# EurorackWizard.net
KiCad netlist of a schematic drawn in EAGLE
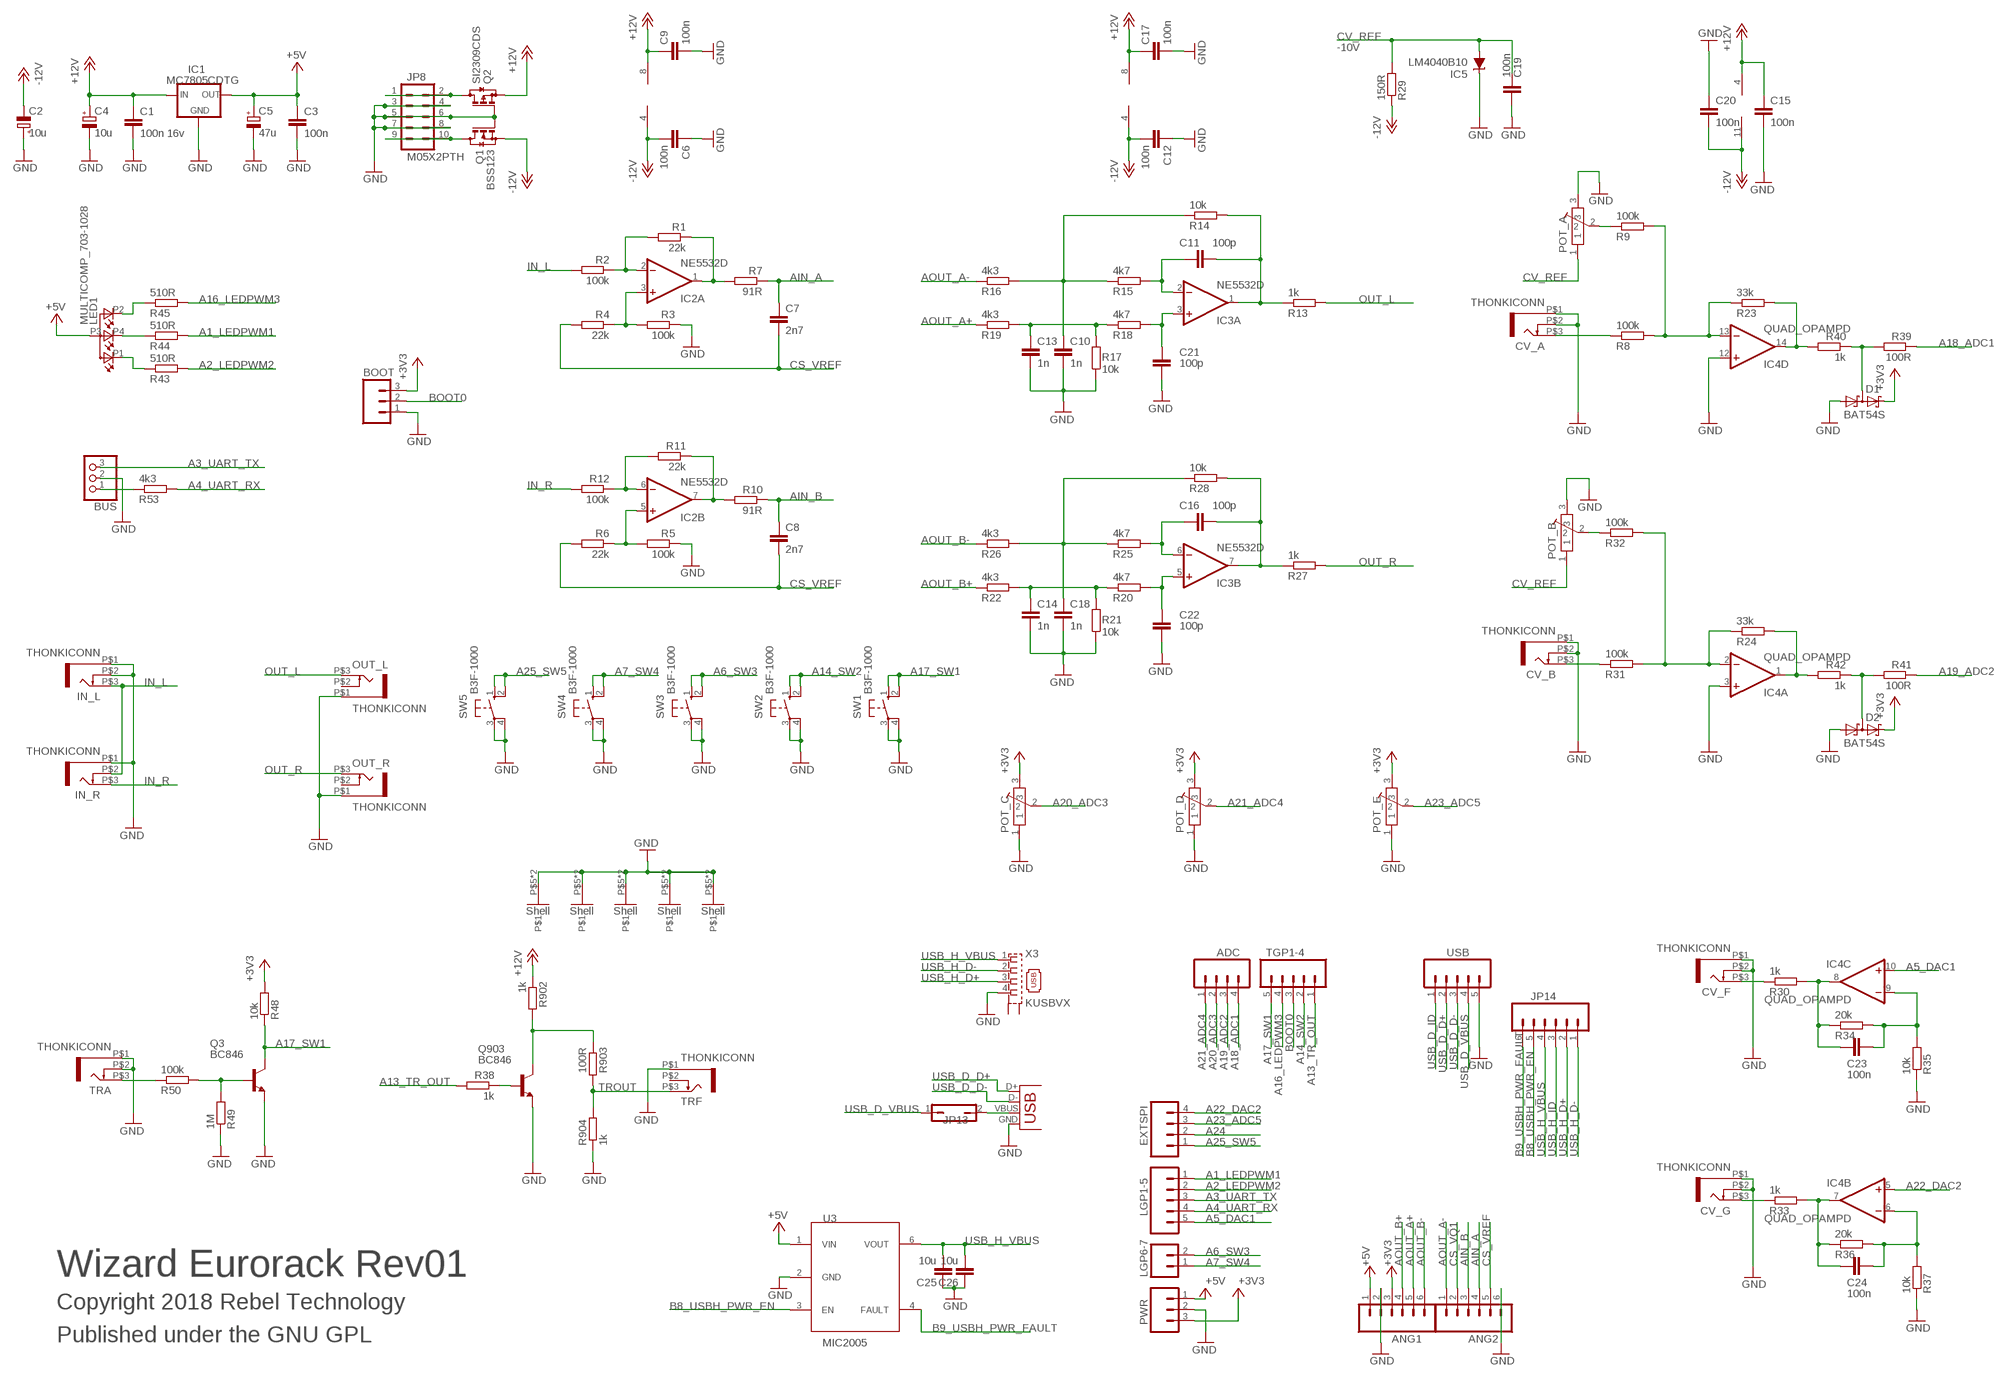
[diagram p0: schematic, sheet 1]

(export (version "E")
  (design (tool "Eeschema 10.0.6"))
  (components
    (comp (ref "ADC")
      (value "M04PTH")
      (footprint "eagle-import:1X04")
      (libsource (lib "eagle-import") (part "M04PTH"))
    )
    (comp (ref "ANG1")
      (value "M06SIP")
      (footprint "eagle-import:1X06")
      (libsource (lib "eagle-import") (part "M06SIP"))
    )
    (comp (ref "ANG2")
      (value "M06SIP")
      (footprint "eagle-import:1X06")
      (libsource (lib "eagle-import") (part "M06SIP"))
    )
    (comp (ref "BOOT")
      (value "M03PTH")
      (footprint "eagle-import:1X03")
      (libsource (lib "eagle-import") (part "M03PTH"))
    )
    (comp (ref "BUS")
      (value "CON-JST-1X03PH-TH")
      (footprint "eagle-import:JST-B3B-PH-KL")
      (libsource (lib "eagle-import") (part "CON-JST-1X03PH-TH"))
    )
    (comp (ref "C1")
      (value "100n 16v")
      (footprint "eagle-import:C0603")
      (libsource (lib "eagle-import") (part "C-EUC0603"))
    )
    (comp (ref "C2")
      (value "10u")
      (footprint "eagle-import:CPOL-5")
      (libsource (lib "eagle-import") (part "CPOL-EU153CLV-0505"))
    )
    (comp (ref "C3")
      (value "100n")
      (footprint "eagle-import:C0603")
      (libsource (lib "eagle-import") (part "C-EUC0603"))
    )
    (comp (ref "C4")
      (value "10u")
      (footprint "eagle-import:CPOL-5")
      (libsource (lib "eagle-import") (part "CPOL-EU153CLV-0505"))
    )
    (comp (ref "C5")
      (value "47u")
      (footprint "eagle-import:PANASONIC_B")
      (libsource (lib "eagle-import") (part "rcl_CPOL-EUB"))
    )
    (comp (ref "C6")
      (value "100n")
      (footprint "eagle-import:C0603")
      (libsource (lib "eagle-import") (part "resistor_C-EUC0603"))
    )
    (comp (ref "C7")
      (value "2n7")
      (footprint "eagle-import:C0603")
      (libsource (lib "eagle-import") (part "resistor_C-EUC0603"))
    )
    (comp (ref "C8")
      (value "2n7")
      (footprint "eagle-import:C0603")
      (libsource (lib "eagle-import") (part "resistor_C-EUC0603"))
    )
    (comp (ref "C9")
      (value "100n")
      (footprint "eagle-import:C0603")
      (libsource (lib "eagle-import") (part "resistor_C-EUC0603"))
    )
    (comp (ref "C10")
      (value "1n")
      (footprint "eagle-import:C0603")
      (libsource (lib "eagle-import") (part "resistor_C-EUC0603"))
    )
    (comp (ref "C11")
      (value "100p")
      (footprint "eagle-import:C0603")
      (libsource (lib "eagle-import") (part "resistor_C-EUC0603"))
    )
    (comp (ref "C12")
      (value "100n")
      (footprint "eagle-import:C0603")
      (libsource (lib "eagle-import") (part "resistor_C-EUC0603"))
    )
    (comp (ref "C13")
      (value "1n")
      (footprint "eagle-import:C0603")
      (libsource (lib "eagle-import") (part "resistor_C-EUC0603"))
    )
    (comp (ref "C14")
      (value "1n")
      (footprint "eagle-import:C0603")
      (libsource (lib "eagle-import") (part "resistor_C-EUC0603"))
    )
    (comp (ref "C15")
      (value "100n")
      (footprint "eagle-import:C0603")
      (libsource (lib "eagle-import") (part "resistor_C-EUC0603"))
    )
    (comp (ref "C16")
      (value "100p")
      (footprint "eagle-import:C0603")
      (libsource (lib "eagle-import") (part "resistor_C-EUC0603"))
    )
    (comp (ref "C17")
      (value "100n")
      (footprint "eagle-import:C0603")
      (libsource (lib "eagle-import") (part "resistor_C-EUC0603"))
    )
    (comp (ref "C18")
      (value "1n")
      (footprint "eagle-import:C0603")
      (libsource (lib "eagle-import") (part "resistor_C-EUC0603"))
    )
    (comp (ref "C19")
      (value "100n")
      (footprint "eagle-import:C0603")
      (libsource (lib "eagle-import") (part "resistor_C-EUC0603"))
    )
    (comp (ref "C20")
      (value "100n")
      (footprint "eagle-import:C0603")
      (libsource (lib "eagle-import") (part "resistor_C-EUC0603"))
    )
    (comp (ref "C21")
      (value "100p")
      (footprint "eagle-import:C0603")
      (libsource (lib "eagle-import") (part "resistor_C-EUC0603"))
    )
    (comp (ref "C22")
      (value "100p")
      (footprint "eagle-import:C0603")
      (libsource (lib "eagle-import") (part "resistor_C-EUC0603"))
    )
    (comp (ref "C23")
      (value "100n")
      (footprint "eagle-import:C0603")
      (libsource (lib "eagle-import") (part "C-EUC0603"))
    )
    (comp (ref "C24")
      (value "100n")
      (footprint "eagle-import:C0603")
      (libsource (lib "eagle-import") (part "C-EUC0603"))
    )
    (comp (ref "C25")
      (value "10u")
      (footprint "eagle-import:C0603")
      (libsource (lib "eagle-import") (part "resistor_C-EUC0603"))
    )
    (comp (ref "C26")
      (value "10u")
      (footprint "eagle-import:C0603")
      (libsource (lib "eagle-import") (part "resistor_C-EUC0603"))
    )
    (comp (ref "CV_A")
      (value "THONKICONN")
      (footprint "eagle-import:THONKICONN")
      (libsource (lib "eagle-import") (part "THONKICONN"))
    )
    (comp (ref "CV_B")
      (value "THONKICONN")
      (footprint "eagle-import:THONKICONN")
      (libsource (lib "eagle-import") (part "THONKICONN"))
    )
    (comp (ref "CV_F")
      (value "THONKICONN")
      (footprint "eagle-import:THONKICONN")
      (libsource (lib "eagle-import") (part "THONKICONN"))
    )
    (comp (ref "CV_G")
      (value "THONKICONN")
      (footprint "eagle-import:THONKICONN")
      (libsource (lib "eagle-import") (part "THONKICONN"))
    )
    (comp (ref "D1")
      (value "BAT54S")
      (footprint "eagle-import:SOT23")
      (libsource (lib "eagle-import") (part "BAT54S"))
    )
    (comp (ref "D2")
      (value "BAT54S")
      (footprint "eagle-import:SOT23")
      (libsource (lib "eagle-import") (part "BAT54S"))
    )
    (comp (ref "EXTSPI")
      (value "M04PTH")
      (footprint "eagle-import:1X04")
      (libsource (lib "eagle-import") (part "M04PTH"))
    )
    (comp (ref "IC1")
      (value "MC7805CDTG")
      (footprint "eagle-import:DPACK")
      (libsource (lib "eagle-import") (part "MC78XX"))
    )
    (comp (ref "IC2")
      (value "NE5532D")
      (footprint "eagle-import:SO08")
      (libsource (lib "eagle-import") (part "NE5532D"))
    )
    (comp (ref "IC3")
      (value "NE5532D")
      (footprint "eagle-import:SO08")
      (libsource (lib "eagle-import") (part "NE5532D"))
    )
    (comp (ref "IC4")
      (value "QUAD_OPAMPD")
      (footprint "eagle-import:SO14")
      (libsource (lib "eagle-import") (part "QUAD_OPAMPD"))
    )
    (comp (ref "IC5")
      (value "LM4040B10")
      (footprint "eagle-import:DBZ_R-PDSO-G3")
      (fields (field (name "MF") "TEXAS INSTRUMENT CONNECTORS") (field (name "MPN") "LM4041C12QDBZT"))
      (libsource (lib "eagle-import") (part "LM4041DBZC12"))
    )
    (comp (ref "IN_L")
      (value "THONKICONN")
      (footprint "eagle-import:THONKICONN")
      (libsource (lib "eagle-import") (part "THONKICONN"))
    )
    (comp (ref "IN_R")
      (value "THONKICONN")
      (footprint "eagle-import:THONKICONN")
      (libsource (lib "eagle-import") (part "THONKICONN"))
    )
    (comp (ref "JP8")
      (value "M05X2PTH")
      (footprint "eagle-import:AVR_ICSP")
      (libsource (lib "eagle-import") (part "M05X2PTH"))
    )
    (comp (ref "JP13")
      (value "JP1Q")
      (footprint "eagle-import:JP1")
      (libsource (lib "eagle-import") (part "JP1Q"))
    )
    (comp (ref "JP14")
      (value "M06SIP")
      (footprint "eagle-import:1X06")
      (libsource (lib "eagle-import") (part "M06SIP"))
    )
    (comp (ref "LED1")
      (value "MULTICOMP_703-1028")
      (footprint "eagle-import:RGB-LED-703-1028")
      (libsource (lib "eagle-import") (part "MULTICOMP_703-1028"))
    )
    (comp (ref "LGP1-5")
      (value "M05PTH")
      (footprint "eagle-import:1X05")
      (libsource (lib "eagle-import") (part "M05PTH"))
    )
    (comp (ref "LGP6-7")
      (value "M02PTH")
      (footprint "eagle-import:1X02")
      (libsource (lib "eagle-import") (part "M02PTH"))
    )
    (comp (ref "OUT_L")
      (value "THONKICONN")
      (footprint "eagle-import:THONKICONN")
      (libsource (lib "eagle-import") (part "THONKICONN"))
    )
    (comp (ref "OUT_R")
      (value "THONKICONN")
      (footprint "eagle-import:THONKICONN")
      (libsource (lib "eagle-import") (part "THONKICONN"))
    )
    (comp (ref "POT_A")
      (value "POT-ALPS-RK09L1140")
      (footprint "eagle-import:POT-ALPS-RK09L1140")
      (libsource (lib "eagle-import") (part "POT-ALPS-RK09L1140"))
    )
    (comp (ref "POT_B")
      (value "POT-ALPS-RK09L1140")
      (footprint "eagle-import:POT-ALPS-RK09L1140")
      (libsource (lib "eagle-import") (part "POT-ALPS-RK09L1140"))
    )
    (comp (ref "POT_C")
      (value "POT-ALPS-RK09L1140")
      (footprint "eagle-import:POT-ALPS-RK09L1140")
      (libsource (lib "eagle-import") (part "POT-ALPS-RK09L1140"))
    )
    (comp (ref "POT_D")
      (value "POT-ALPS-RK09L1140")
      (footprint "eagle-import:POT-ALPS-RK09L1140")
      (libsource (lib "eagle-import") (part "POT-ALPS-RK09L1140"))
    )
    (comp (ref "POT_E")
      (value "POT-ALPS-RK09L1140")
      (footprint "eagle-import:POT-ALPS-RK09L1140")
      (libsource (lib "eagle-import") (part "POT-ALPS-RK09L1140"))
    )
    (comp (ref "PWR")
      (value "M03PTH")
      (footprint "eagle-import:1X03")
      (libsource (lib "eagle-import") (part "M03PTH"))
    )
    (comp (ref "Q1")
      (value "BSS123")
      (footprint "eagle-import:SOT23")
      (libsource (lib "eagle-import") (part "BSS123"))
    )
    (comp (ref "Q2")
      (value "SI2309CDS")
      (footprint "eagle-import:SOT23")
      (libsource (lib "eagle-import") (part "BSS84"))
    )
    (comp (ref "Q3")
      (value "BC846")
      (footprint "eagle-import:SOT23")
      (libsource (lib "eagle-import") (part "BC846"))
    )
    (comp (ref "Q903")
      (value "BC846")
      (footprint "eagle-import:SOT23")
      (libsource (lib "eagle-import") (part "BC846"))
    )
    (comp (ref "R1")
      (value "22k")
      (footprint "eagle-import:0603")
      (libsource (lib "eagle-import") (part "R-EU_0603"))
    )
    (comp (ref "R2")
      (value "100k")
      (footprint "eagle-import:0603")
      (libsource (lib "eagle-import") (part "R-EU_0603"))
    )
    (comp (ref "R3")
      (value "100k")
      (footprint "eagle-import:0603")
      (libsource (lib "eagle-import") (part "R-EU_0603"))
    )
    (comp (ref "R4")
      (value "22k")
      (footprint "eagle-import:0603")
      (libsource (lib "eagle-import") (part "R-EU_0603"))
    )
    (comp (ref "R5")
      (value "100k")
      (footprint "eagle-import:0603")
      (libsource (lib "eagle-import") (part "R-EU_0603"))
    )
    (comp (ref "R6")
      (value "22k")
      (footprint "eagle-import:0603")
      (libsource (lib "eagle-import") (part "R-EU_0603"))
    )
    (comp (ref "R7")
      (value "91R")
      (footprint "eagle-import:0603")
      (libsource (lib "eagle-import") (part "R-EU_0603"))
    )
    (comp (ref "R8")
      (value "100k")
      (footprint "eagle-import:0603")
      (libsource (lib "eagle-import") (part "R-EU_0603"))
    )
    (comp (ref "R9")
      (value "100k")
      (footprint "eagle-import:0603")
      (libsource (lib "eagle-import") (part "R-EU_0603"))
    )
    (comp (ref "R10")
      (value "91R")
      (footprint "eagle-import:0603")
      (libsource (lib "eagle-import") (part "R-EU_0603"))
    )
    (comp (ref "R11")
      (value "22k")
      (footprint "eagle-import:0603")
      (libsource (lib "eagle-import") (part "R-EU_0603"))
    )
    (comp (ref "R12")
      (value "100k")
      (footprint "eagle-import:0603")
      (libsource (lib "eagle-import") (part "R-EU_0603"))
    )
    (comp (ref "R13")
      (value "1k")
      (footprint "eagle-import:0603")
      (libsource (lib "eagle-import") (part "R-EU_0603"))
    )
    (comp (ref "R14")
      (value "10k")
      (footprint "eagle-import:0603")
      (libsource (lib "eagle-import") (part "R-EU_0603"))
    )
    (comp (ref "R15")
      (value "4k7")
      (footprint "eagle-import:0603")
      (libsource (lib "eagle-import") (part "R-EU_0603"))
    )
    (comp (ref "R16")
      (value "4k3")
      (footprint "eagle-import:0603")
      (libsource (lib "eagle-import") (part "R-EU_0603"))
    )
    (comp (ref "R17")
      (value "10k")
      (footprint "eagle-import:0603")
      (libsource (lib "eagle-import") (part "R-EU_0603"))
    )
    (comp (ref "R18")
      (value "4k7")
      (footprint "eagle-import:0603")
      (libsource (lib "eagle-import") (part "R-EU_0603"))
    )
    (comp (ref "R19")
      (value "4k3")
      (footprint "eagle-import:0603")
      (libsource (lib "eagle-import") (part "R-EU_0603"))
    )
    (comp (ref "R20")
      (value "4k7")
      (footprint "eagle-import:0603")
      (libsource (lib "eagle-import") (part "R-EU_0603"))
    )
    (comp (ref "R21")
      (value "10k")
      (footprint "eagle-import:0603")
      (libsource (lib "eagle-import") (part "R-EU_0603"))
    )
    (comp (ref "R22")
      (value "4k3")
      (footprint "eagle-import:0603")
      (libsource (lib "eagle-import") (part "R-EU_0603"))
    )
    (comp (ref "R23")
      (value "33k")
      (footprint "eagle-import:0603")
      (libsource (lib "eagle-import") (part "R-EU_0603"))
    )
    (comp (ref "R24")
      (value "33k")
      (footprint "eagle-import:0603")
      (libsource (lib "eagle-import") (part "R-EU_0603"))
    )
    (comp (ref "R25")
      (value "4k7")
      (footprint "eagle-import:0603")
      (libsource (lib "eagle-import") (part "R-EU_0603"))
    )
    (comp (ref "R26")
      (value "4k3")
      (footprint "eagle-import:0603")
      (libsource (lib "eagle-import") (part "R-EU_0603"))
    )
    (comp (ref "R27")
      (value "1k")
      (footprint "eagle-import:0603")
      (libsource (lib "eagle-import") (part "R-EU_0603"))
    )
    (comp (ref "R28")
      (value "10k")
      (footprint "eagle-import:0603")
      (libsource (lib "eagle-import") (part "R-EU_0603"))
    )
    (comp (ref "R29")
      (value "150R")
      (footprint "eagle-import:0603")
      (libsource (lib "eagle-import") (part "R-EU_0603"))
    )
    (comp (ref "R30")
      (value "1k")
      (footprint "eagle-import:0603")
      (libsource (lib "eagle-import") (part "R-EU_0603"))
    )
    (comp (ref "R31")
      (value "100k")
      (footprint "eagle-import:0603")
      (libsource (lib "eagle-import") (part "R-EU_0603"))
    )
    (comp (ref "R32")
      (value "100k")
      (footprint "eagle-import:0603")
      (libsource (lib "eagle-import") (part "R-EU_0603"))
    )
    (comp (ref "R33")
      (value "1k")
      (footprint "eagle-import:0603")
      (libsource (lib "eagle-import") (part "R-EU_0603"))
    )
    (comp (ref "R34")
      (value "20k")
      (footprint "eagle-import:0603")
      (libsource (lib "eagle-import") (part "R-EU_0603"))
    )
    (comp (ref "R35")
      (value "10k")
      (footprint "eagle-import:0603")
      (libsource (lib "eagle-import") (part "R-EU_0603"))
    )
    (comp (ref "R36")
      (value "20k")
      (footprint "eagle-import:0603")
      (libsource (lib "eagle-import") (part "R-EU_0603"))
    )
    (comp (ref "R37")
      (value "10k")
      (footprint "eagle-import:0603")
      (libsource (lib "eagle-import") (part "R-EU_0603"))
    )
    (comp (ref "R38")
      (value "1k")
      (footprint "eagle-import:0603")
      (libsource (lib "eagle-import") (part "R-EU_0603"))
    )
    (comp (ref "R39")
      (value "100R")
      (footprint "eagle-import:0603")
      (libsource (lib "eagle-import") (part "R-EU_0603"))
    )
    (comp (ref "R40")
      (value "1k")
      (footprint "eagle-import:0603")
      (libsource (lib "eagle-import") (part "R-EU_0603"))
    )
    (comp (ref "R41")
      (value "100R")
      (footprint "eagle-import:0603")
      (libsource (lib "eagle-import") (part "R-EU_0603"))
    )
    (comp (ref "R42")
      (value "1k")
      (footprint "eagle-import:0603")
      (libsource (lib "eagle-import") (part "R-EU_0603"))
    )
    (comp (ref "R43")
      (value "510R")
      (footprint "eagle-import:0603")
      (libsource (lib "eagle-import") (part "R-EU_0603"))
    )
    (comp (ref "R44")
      (value "510R")
      (footprint "eagle-import:0603")
      (libsource (lib "eagle-import") (part "R-EU_0603"))
    )
    (comp (ref "R45")
      (value "510R")
      (footprint "eagle-import:0603")
      (libsource (lib "eagle-import") (part "R-EU_0603"))
    )
    (comp (ref "R48")
      (value "10k")
      (footprint "eagle-import:0603")
      (libsource (lib "eagle-import") (part "R-EU_0603"))
    )
    (comp (ref "R49")
      (value "1M")
      (footprint "eagle-import:0603")
      (libsource (lib "eagle-import") (part "R-EU_0603"))
    )
    (comp (ref "R50")
      (value "100k")
      (footprint "eagle-import:0603")
      (libsource (lib "eagle-import") (part "R-EU_0603"))
    )
    (comp (ref "R53")
      (value "4k3")
      (footprint "eagle-import:0603")
      (libsource (lib "eagle-import") (part "R-EU_0603"))
    )
    (comp (ref "R902")
      (value "1k")
      (footprint "eagle-import:0603")
      (libsource (lib "eagle-import") (part "R-EU_0603"))
    )
    (comp (ref "R903")
      (value "100R")
      (footprint "eagle-import:0603")
      (libsource (lib "eagle-import") (part "R-EU_0603"))
    )
    (comp (ref "R904")
      (value "1k")
      (footprint "eagle-import:0603")
      (libsource (lib "eagle-import") (part "R-EU_0603"))
    )
    (comp (ref "SW1")
      (value "B3F-1000")
      (footprint "eagle-import:B3F-10XX")
      (libsource (lib "eagle-import") (part "10-XX"))
    )
    (comp (ref "SW2")
      (value "B3F-1000")
      (footprint "eagle-import:B3F-10XX")
      (libsource (lib "eagle-import") (part "10-XX"))
    )
    (comp (ref "SW3")
      (value "B3F-1000")
      (footprint "eagle-import:B3F-10XX")
      (libsource (lib "eagle-import") (part "10-XX"))
    )
    (comp (ref "SW4")
      (value "B3F-1000")
      (footprint "eagle-import:B3F-10XX")
      (libsource (lib "eagle-import") (part "10-XX"))
    )
    (comp (ref "SW5")
      (value "B3F-1000")
      (footprint "eagle-import:B3F-10XX")
      (libsource (lib "eagle-import") (part "10-XX"))
    )
    (comp (ref "TGP1-4")
      (value "M05PTH")
      (footprint "eagle-import:1X05")
      (libsource (lib "eagle-import") (part "M05PTH"))
    )
    (comp (ref "TRA")
      (value "THONKICONN")
      (footprint "eagle-import:THONKICONN")
      (libsource (lib "eagle-import") (part "THONKICONN"))
    )
    (comp (ref "TRF")
      (value "THONKICONN")
      (footprint "eagle-import:THONKICONN")
      (libsource (lib "eagle-import") (part "THONKICONN"))
    )
    (comp (ref "U3")
      (value "MIC2005")
      (footprint "eagle-import:SOT23-6")
      (libsource (lib "eagle-import") (part "MIC2005"))
    )
    (comp (ref "USB")
      (value "M05PTH")
      (footprint "eagle-import:1X05")
      (libsource (lib "eagle-import") (part "M05PTH"))
    )
    (comp (ref "X3")
      (value "KUSBVX")
      (footprint "eagle-import:KUSBVX")
      (libsource (lib "eagle-import") (part "KUSBVX"))
    )
    (comp (ref "X5")
      (value "USBPTH-VERTICAL")
      (footprint "eagle-import:USB-B-PTH-VERTICAL")
      (libsource (lib "eagle-import") (part "USBPTH-VERTICAL"))
    )
  )
  (nets
    (net (code "1") (name "+3V3") (class "Default")
      (node (ref "ANG1") (pin "3") (pinfunction "3_3") (pintype "passive"))
      (node (ref "BOOT") (pin "3") (pinfunction "3_3") (pintype "passive"))
      (node (ref "D1") (pin "2") (pinfunction "C2_2") (pintype "passive"))
      (node (ref "D2") (pin "2") (pinfunction "C2_2") (pintype "passive"))
      (node (ref "POT_C") (pin "3") (pinfunction "3_3") (pintype "bidirectional"))
      (node (ref "POT_D") (pin "3") (pinfunction "3_3") (pintype "bidirectional"))
      (node (ref "POT_E") (pin "3") (pinfunction "3_3") (pintype "bidirectional"))
      (node (ref "PWR") (pin "3") (pinfunction "3_3") (pintype "passive"))
      (node (ref "R48") (pin "2") (pinfunction "2_2") (pintype "passive"))
    )
    (net (code "2") (name "+5V") (class "Default")
      (node (ref "ANG1") (pin "1") (pinfunction "1_1") (pintype "passive"))
      (node (ref "C3") (pin "1") (pinfunction "1_1") (pintype "passive"))
      (node (ref "C5") (pin "+") (pinfunction "+_+") (pintype "passive"))
      (node (ref "IC1") (pin "3") (pinfunction "OUT_3") (pintype "passive"))
      (node (ref "LED1") (pin "P3") (pinfunction "A_P3") (pintype "passive"))
      (node (ref "PWR") (pin "1") (pinfunction "1_1") (pintype "passive"))
      (node (ref "U3") (pin "1") (pinfunction "VIN_1") (pintype "power_in"))
    )
    (net (code "3") (name "+12V") (class "Default")
      (node (ref "C1") (pin "1") (pinfunction "1_1") (pintype "passive"))
      (node (ref "C15") (pin "1") (pinfunction "1_1") (pintype "passive"))
      (node (ref "C17") (pin "1") (pinfunction "1_1") (pintype "passive"))
      (node (ref "C4") (pin "+") (pinfunction "+_+") (pintype "passive"))
      (node (ref "C9") (pin "1") (pinfunction "1_1") (pintype "passive"))
      (node (ref "IC1") (pin "1") (pinfunction "IN_1") (pintype "input"))
      (node (ref "IC2") (pin "8") (pinfunction "V+_8") (pintype "power_in"))
      (node (ref "IC3") (pin "8") (pinfunction "V+_8") (pintype "power_in"))
      (node (ref "IC4") (pin "4") (pinfunction "V+_4") (pintype "power_in"))
      (node (ref "Q2") (pin "2") (pinfunction "S_2") (pintype "passive"))
      (node (ref "R902") (pin "1") (pinfunction "1_1") (pintype "passive"))
    )
    (net (code "4") (name "-12V") (class "Default")
      (node (ref "C12") (pin "2") (pinfunction "2_2") (pintype "passive"))
      (node (ref "C2") (pin "-") (pinfunction "-_-") (pintype "passive"))
      (node (ref "C20") (pin "2") (pinfunction "2_2") (pintype "passive"))
      (node (ref "C6") (pin "2") (pinfunction "2_2") (pintype "passive"))
      (node (ref "IC2") (pin "4") (pinfunction "V-_4") (pintype "power_in"))
      (node (ref "IC3") (pin "4") (pinfunction "V-_4") (pintype "power_in"))
      (node (ref "IC4") (pin "11") (pinfunction "V-_11") (pintype "power_in"))
      (node (ref "Q1") (pin "2") (pinfunction "S_2") (pintype "passive"))
      (node (ref "R29") (pin "1") (pinfunction "1_1") (pintype "passive"))
    )
    (net (code "5") (name "/A1_LEDPWM1") (class "Default")
      (node (ref "LGP1-5") (pin "1") (pinfunction "1_1") (pintype "passive"))
      (node (ref "R44") (pin "2") (pinfunction "2_2") (pintype "passive"))
    )
    (net (code "6") (name "/A2_LEDPWM2") (class "Default")
      (node (ref "LGP1-5") (pin "2") (pinfunction "2_2") (pintype "passive"))
      (node (ref "R43") (pin "2") (pinfunction "2_2") (pintype "passive"))
    )
    (net (code "7") (name "/A3_UART_TX") (class "Default")
      (node (ref "BUS") (pin "3") (pinfunction "3_3") (pintype "passive"))
      (node (ref "LGP1-5") (pin "3") (pinfunction "3_3") (pintype "passive"))
    )
    (net (code "8") (name "/A4_UART_RX") (class "Default")
      (node (ref "LGP1-5") (pin "4") (pinfunction "4_4") (pintype "passive"))
      (node (ref "R53") (pin "2") (pinfunction "2_2") (pintype "passive"))
    )
    (net (code "9") (name "/A5_DAC1") (class "Default")
      (node (ref "IC4") (pin "10") (pinfunction "+IN_10") (pintype "input"))
      (node (ref "LGP1-5") (pin "5") (pinfunction "5_5") (pintype "passive"))
    )
    (net (code "10") (name "/A6_SW3") (class "Default")
      (node (ref "LGP6-7") (pin "2") (pinfunction "2_2") (pintype "passive"))
      (node (ref "SW3") (pin "1") (pinfunction "S_1") (pintype "passive"))
      (node (ref "SW3") (pin "2") (pinfunction "S1_2") (pintype "passive"))
    )
    (net (code "11") (name "/A7_SW4") (class "Default")
      (node (ref "LGP6-7") (pin "1") (pinfunction "1_1") (pintype "passive"))
      (node (ref "SW4") (pin "1") (pinfunction "S_1") (pintype "passive"))
      (node (ref "SW4") (pin "2") (pinfunction "S1_2") (pintype "passive"))
    )
    (net (code "12") (name "/A13_TR_OUT") (class "Default")
      (node (ref "R38") (pin "2") (pinfunction "2_2") (pintype "passive"))
      (node (ref "TGP1-4") (pin "1") (pinfunction "1_1") (pintype "passive"))
    )
    (net (code "13") (name "/A14_SW2") (class "Default")
      (node (ref "SW2") (pin "1") (pinfunction "S_1") (pintype "passive"))
      (node (ref "SW2") (pin "2") (pinfunction "S1_2") (pintype "passive"))
      (node (ref "TGP1-4") (pin "2") (pinfunction "2_2") (pintype "passive"))
    )
    (net (code "14") (name "/A16_LEDPWM3") (class "Default")
      (node (ref "R45") (pin "2") (pinfunction "2_2") (pintype "passive"))
      (node (ref "TGP1-4") (pin "4") (pinfunction "4_4") (pintype "passive"))
    )
    (net (code "15") (name "/A17_SW1") (class "Default")
      (node (ref "Q3") (pin "3") (pinfunction "C_3") (pintype "passive"))
      (node (ref "R48") (pin "1") (pinfunction "1_1") (pintype "passive"))
      (node (ref "SW1") (pin "1") (pinfunction "S_1") (pintype "passive"))
      (node (ref "SW1") (pin "2") (pinfunction "S1_2") (pintype "passive"))
      (node (ref "TGP1-4") (pin "5") (pinfunction "5_5") (pintype "passive"))
    )
    (net (code "16") (name "/A18_ADC1") (class "Default")
      (node (ref "ADC") (pin "4") (pinfunction "4_4") (pintype "passive"))
      (node (ref "R39") (pin "1") (pinfunction "1_1") (pintype "passive"))
    )
    (net (code "17") (name "/A19_ADC2") (class "Default")
      (node (ref "ADC") (pin "3") (pinfunction "3_3") (pintype "passive"))
      (node (ref "R41") (pin "1") (pinfunction "1_1") (pintype "passive"))
    )
    (net (code "18") (name "/A20_ADC3") (class "Default")
      (node (ref "ADC") (pin "2") (pinfunction "2_2") (pintype "passive"))
      (node (ref "POT_C") (pin "2") (pinfunction "2_2") (pintype "bidirectional"))
    )
    (net (code "19") (name "/A21_ADC4") (class "Default")
      (node (ref "ADC") (pin "1") (pinfunction "1_1") (pintype "passive"))
      (node (ref "POT_D") (pin "2") (pinfunction "2_2") (pintype "bidirectional"))
    )
    (net (code "20") (name "/A22_DAC2") (class "Default")
      (node (ref "EXTSPI") (pin "4") (pinfunction "4_4") (pintype "passive"))
      (node (ref "IC4") (pin "5") (pinfunction "+IN_5") (pintype "input"))
    )
    (net (code "21") (name "/A23_ADC5") (class "Default")
      (node (ref "EXTSPI") (pin "3") (pinfunction "3_3") (pintype "passive"))
      (node (ref "POT_E") (pin "2") (pinfunction "2_2") (pintype "bidirectional"))
    )
    (net (code "22") (name "/A24") (class "Default")
      (node (ref "EXTSPI") (pin "2") (pinfunction "2_2") (pintype "passive"))
    )
    (net (code "23") (name "/A25_SW5") (class "Default")
      (node (ref "EXTSPI") (pin "1") (pinfunction "1_1") (pintype "passive"))
      (node (ref "SW5") (pin "1") (pinfunction "S_1") (pintype "passive"))
      (node (ref "SW5") (pin "2") (pinfunction "S1_2") (pintype "passive"))
    )
    (net (code "24") (name "/AIN_A") (class "Default")
      (node (ref "ANG2") (pin "4") (pinfunction "4_4") (pintype "passive"))
      (node (ref "C7") (pin "1") (pinfunction "1_1") (pintype "passive"))
      (node (ref "R7") (pin "1") (pinfunction "1_1") (pintype "passive"))
    )
    (net (code "25") (name "/AIN_B") (class "Default")
      (node (ref "ANG2") (pin "3") (pinfunction "3_3") (pintype "passive"))
      (node (ref "C8") (pin "1") (pinfunction "1_1") (pintype "passive"))
      (node (ref "R10") (pin "1") (pinfunction "1_1") (pintype "passive"))
    )
    (net (code "26") (name "/AOUT_A+") (class "Default")
      (node (ref "ANG1") (pin "5") (pinfunction "5_5") (pintype "passive"))
      (node (ref "R19") (pin "1") (pinfunction "1_1") (pintype "passive"))
    )
    (net (code "27") (name "/AOUT_A-") (class "Default")
      (node (ref "ANG2") (pin "1") (pinfunction "1_1") (pintype "passive"))
      (node (ref "R16") (pin "1") (pinfunction "1_1") (pintype "passive"))
    )
    (net (code "28") (name "/AOUT_B+") (class "Default")
      (node (ref "ANG1") (pin "4") (pinfunction "4_4") (pintype "passive"))
      (node (ref "R22") (pin "1") (pinfunction "1_1") (pintype "passive"))
    )
    (net (code "29") (name "/AOUT_B-") (class "Default")
      (node (ref "ANG1") (pin "6") (pinfunction "6_6") (pintype "passive"))
      (node (ref "R26") (pin "1") (pinfunction "1_1") (pintype "passive"))
    )
    (net (code "30") (name "/B8_USBH_PWR_EN") (class "Default")
      (node (ref "JP14") (pin "5") (pinfunction "5_5") (pintype "passive"))
      (node (ref "U3") (pin "3") (pinfunction "EN_3") (pintype "input"))
    )
    (net (code "31") (name "/B9_USBH_PWR_FAULT") (class "Default")
      (node (ref "JP14") (pin "6") (pinfunction "6_6") (pintype "passive"))
      (node (ref "U3") (pin "4") (pinfunction "FAULT_4") (pintype "output"))
    )
    (net (code "32") (name "/BOOT0") (class "Default")
      (node (ref "BOOT") (pin "2") (pinfunction "2_2") (pintype "passive"))
      (node (ref "TGP1-4") (pin "3") (pinfunction "3_3") (pintype "passive"))
    )
    (net (code "33") (name "/CS_VQ1") (class "Default")
      (node (ref "ANG2") (pin "2") (pinfunction "2_2") (pintype "passive"))
    )
    (net (code "34") (name "/CS_VREF") (class "Default")
      (node (ref "ANG2") (pin "5") (pinfunction "5_5") (pintype "passive"))
      (node (ref "C7") (pin "2") (pinfunction "2_2") (pintype "passive"))
      (node (ref "C8") (pin "2") (pinfunction "2_2") (pintype "passive"))
      (node (ref "R4") (pin "2") (pinfunction "2_2") (pintype "passive"))
      (node (ref "R6") (pin "2") (pinfunction "2_2") (pintype "passive"))
    )
    (net (code "35") (name "/CV_REF") (class "Default")
      (node (ref "C19") (pin "1") (pinfunction "1_1") (pintype "passive"))
      (node (ref "IC5") (pin "2") (pinfunction "A_2") (pintype "passive"))
      (node (ref "POT_A") (pin "1") (pinfunction "1_1") (pintype "bidirectional"))
      (node (ref "POT_B") (pin "1") (pinfunction "1_1") (pintype "bidirectional"))
      (node (ref "R29") (pin "2") (pinfunction "2_2") (pintype "passive"))
    )
    (net (code "36") (name "/IN_L") (class "Default")
      (node (ref "IN_L") (pin "P$3") (pinfunction "3_P$3") (pintype "passive"))
      (node (ref "IN_R") (pin "P$2") (pinfunction "4_P$2") (pintype "passive"))
      (node (ref "R2") (pin "2") (pinfunction "2_2") (pintype "passive"))
    )
    (net (code "37") (name "/IN_R") (class "Default")
      (node (ref "IN_R") (pin "P$3") (pinfunction "3_P$3") (pintype "passive"))
      (node (ref "R12") (pin "2") (pinfunction "2_2") (pintype "passive"))
    )
    (net (code "38") (name "/OUT_L") (class "Default")
      (node (ref "OUT_L") (pin "P$3") (pinfunction "3_P$3") (pintype "passive"))
      (node (ref "R13") (pin "2") (pinfunction "2_2") (pintype "passive"))
    )
    (net (code "39") (name "/OUT_R") (class "Default")
      (node (ref "OUT_R") (pin "P$3") (pinfunction "3_P$3") (pintype "passive"))
      (node (ref "R27") (pin "2") (pinfunction "2_2") (pintype "passive"))
    )
    (net (code "40") (name "/TROUT") (class "Default")
      (node (ref "R903") (pin "2") (pinfunction "2_2") (pintype "passive"))
      (node (ref "R904") (pin "2") (pinfunction "2_2") (pintype "passive"))
      (node (ref "TRF") (pin "P$3") (pinfunction "3_P$3") (pintype "passive"))
    )
    (net (code "41") (name "/USB_D_D+") (class "Default")
      (node (ref "USB") (pin "2") (pinfunction "2_2") (pintype "passive"))
      (node (ref "X5") (pin "D+") (pinfunction "D+_D+") (pintype "bidirectional"))
    )
    (net (code "42") (name "/USB_D_D-") (class "Default")
      (node (ref "USB") (pin "3") (pinfunction "3_3") (pintype "passive"))
      (node (ref "X5") (pin "D-") (pinfunction "D-_D-") (pintype "bidirectional"))
    )
    (net (code "43") (name "/USB_D_ID") (class "Default")
      (node (ref "USB") (pin "1") (pinfunction "1_1") (pintype "passive"))
    )
    (net (code "44") (name "/USB_D_VBUS") (class "Default")
      (node (ref "JP13") (pin "1") (pinfunction "1_1") (pintype "passive"))
      (node (ref "USB") (pin "4") (pinfunction "4_4") (pintype "passive"))
    )
    (net (code "45") (name "/USB_H_D+") (class "Default")
      (node (ref "JP14") (pin "2") (pinfunction "2_2") (pintype "passive"))
      (node (ref "X3") (pin "3") (pinfunction "3_3") (pintype "passive"))
    )
    (net (code "46") (name "/USB_H_D-") (class "Default")
      (node (ref "JP14") (pin "1") (pinfunction "1_1") (pintype "passive"))
      (node (ref "X3") (pin "2") (pinfunction "2_2") (pintype "passive"))
    )
    (net (code "47") (name "/USB_H_ID") (class "Default")
      (node (ref "JP14") (pin "3") (pinfunction "3_3") (pintype "passive"))
    )
    (net (code "48") (name "/USB_H_VBUS") (class "Default")
      (node (ref "C25") (pin "2") (pinfunction "2_2") (pintype "passive"))
      (node (ref "C26") (pin "2") (pinfunction "2_2") (pintype "passive"))
      (node (ref "JP14") (pin "4") (pinfunction "4_4") (pintype "passive"))
      (node (ref "U3") (pin "6") (pinfunction "VOUT_6") (pintype "output"))
      (node (ref "X3") (pin "1") (pinfunction "1_1") (pintype "passive"))
    )
    (net (code "49") (name "GND") (class "Default")
      (node (ref "ANG1") (pin "2") (pinfunction "2_2") (pintype "passive"))
      (node (ref "ANG2") (pin "6") (pinfunction "6_6") (pintype "passive"))
      (node (ref "BOOT") (pin "1") (pinfunction "1_1") (pintype "passive"))
      (node (ref "BUS") (pin "2") (pinfunction "2_2") (pintype "passive"))
      (node (ref "C1") (pin "2") (pinfunction "2_2") (pintype "passive"))
      (node (ref "C10") (pin "2") (pinfunction "2_2") (pintype "passive"))
      (node (ref "C12") (pin "1") (pinfunction "1_1") (pintype "passive"))
      (node (ref "C13") (pin "2") (pinfunction "2_2") (pintype "passive"))
      (node (ref "C14") (pin "2") (pinfunction "2_2") (pintype "passive"))
      (node (ref "C15") (pin "2") (pinfunction "2_2") (pintype "passive"))
      (node (ref "C17") (pin "2") (pinfunction "2_2") (pintype "passive"))
      (node (ref "C18") (pin "2") (pinfunction "2_2") (pintype "passive"))
      (node (ref "C19") (pin "2") (pinfunction "2_2") (pintype "passive"))
      (node (ref "C2") (pin "+") (pinfunction "+_+") (pintype "passive"))
      (node (ref "C20") (pin "1") (pinfunction "1_1") (pintype "passive"))
      (node (ref "C21") (pin "2") (pinfunction "2_2") (pintype "passive"))
      (node (ref "C22") (pin "2") (pinfunction "2_2") (pintype "passive"))
      (node (ref "C25") (pin "1") (pinfunction "1_1") (pintype "passive"))
      (node (ref "C26") (pin "1") (pinfunction "1_1") (pintype "passive"))
      (node (ref "C3") (pin "2") (pinfunction "2_2") (pintype "passive"))
      (node (ref "C4") (pin "-") (pinfunction "-_-") (pintype "passive"))
      (node (ref "C5") (pin "-") (pinfunction "-_-") (pintype "passive"))
      (node (ref "C6") (pin "1") (pinfunction "1_1") (pintype "passive"))
      (node (ref "C9") (pin "2") (pinfunction "2_2") (pintype "passive"))
      (node (ref "CV_A") (pin "P$1") (pinfunction "5_P$1") (pintype "passive"))
      (node (ref "CV_A") (pin "P$2") (pinfunction "4_P$2") (pintype "passive"))
      (node (ref "CV_B") (pin "P$1") (pinfunction "5_P$1") (pintype "passive"))
      (node (ref "CV_B") (pin "P$2") (pinfunction "4_P$2") (pintype "passive"))
      (node (ref "CV_F") (pin "P$1") (pinfunction "5_P$1") (pintype "passive"))
      (node (ref "CV_F") (pin "P$2") (pinfunction "4_P$2") (pintype "passive"))
      (node (ref "CV_G") (pin "P$1") (pinfunction "5_P$1") (pintype "passive"))
      (node (ref "CV_G") (pin "P$2") (pinfunction "4_P$2") (pintype "passive"))
      (node (ref "D1") (pin "1") (pinfunction "A1_1") (pintype "passive"))
      (node (ref "D2") (pin "1") (pinfunction "A1_1") (pintype "passive"))
      (node (ref "IC1") (pin "4") (pinfunction "GND_4") (pintype "input"))
      (node (ref "IC4") (pin "12") (pinfunction "+IN_12") (pintype "input"))
      (node (ref "IC4") (pin "3") (pinfunction "+IN_3") (pintype "input"))
      (node (ref "IC5") (pin "1") (pinfunction "C_1") (pintype "passive"))
      (node (ref "IN_L") (pin "P$1") (pinfunction "5_P$1") (pintype "passive"))
      (node (ref "IN_L") (pin "P$2") (pinfunction "4_P$2") (pintype "passive"))
      (node (ref "IN_R") (pin "P$1") (pinfunction "5_P$1") (pintype "passive"))
      (node (ref "JP8") (pin "3") (pinfunction "3_3") (pintype "passive"))
      (node (ref "JP8") (pin "4") (pinfunction "4_4") (pintype "passive"))
      (node (ref "JP8") (pin "5") (pinfunction "5_5") (pintype "passive"))
      (node (ref "JP8") (pin "6") (pinfunction "6_6") (pintype "passive"))
      (node (ref "JP8") (pin "7") (pinfunction "7_7") (pintype "passive"))
      (node (ref "JP8") (pin "8") (pinfunction "8_8") (pintype "passive"))
      (node (ref "OUT_L") (pin "P$1") (pinfunction "5_P$1") (pintype "passive"))
      (node (ref "OUT_R") (pin "P$1") (pinfunction "5_P$1") (pintype "passive"))
      (node (ref "POT_A") (pin "3") (pinfunction "3_3") (pintype "bidirectional"))
      (node (ref "POT_A") (pin "P$5") (pinfunction "P$1_P$5") (pintype "bidirectional"))
      (node (ref "POT_A") (pin "P$6") (pinfunction "P$1_P$6") (pintype "bidirectional"))
      (node (ref "POT_B") (pin "3") (pinfunction "3_3") (pintype "bidirectional"))
      (node (ref "POT_B") (pin "P$5") (pinfunction "P$1_P$5") (pintype "bidirectional"))
      (node (ref "POT_B") (pin "P$6") (pinfunction "P$1_P$6") (pintype "bidirectional"))
      (node (ref "POT_C") (pin "1") (pinfunction "1_1") (pintype "bidirectional"))
      (node (ref "POT_C") (pin "P$5") (pinfunction "P$1_P$5") (pintype "bidirectional"))
      (node (ref "POT_C") (pin "P$6") (pinfunction "P$1_P$6") (pintype "bidirectional"))
      (node (ref "POT_D") (pin "1") (pinfunction "1_1") (pintype "bidirectional"))
      (node (ref "POT_D") (pin "P$5") (pinfunction "P$1_P$5") (pintype "bidirectional"))
      (node (ref "POT_D") (pin "P$6") (pinfunction "P$1_P$6") (pintype "bidirectional"))
      (node (ref "POT_E") (pin "1") (pinfunction "1_1") (pintype "bidirectional"))
      (node (ref "POT_E") (pin "P$5") (pinfunction "P$1_P$5") (pintype "bidirectional"))
      (node (ref "POT_E") (pin "P$6") (pinfunction "P$1_P$6") (pintype "bidirectional"))
      (node (ref "PWR") (pin "2") (pinfunction "2_2") (pintype "passive"))
      (node (ref "Q1") (pin "1") (pinfunction "G_1") (pintype "passive"))
      (node (ref "Q2") (pin "1") (pinfunction "G_1") (pintype "passive"))
      (node (ref "Q3") (pin "2") (pinfunction "E_2") (pintype "passive"))
      (node (ref "Q903") (pin "2") (pinfunction "E_2") (pintype "passive"))
      (node (ref "R17") (pin "1") (pinfunction "1_1") (pintype "passive"))
      (node (ref "R21") (pin "1") (pinfunction "1_1") (pintype "passive"))
      (node (ref "R3") (pin "1") (pinfunction "1_1") (pintype "passive"))
      (node (ref "R35") (pin "1") (pinfunction "1_1") (pintype "passive"))
      (node (ref "R37") (pin "1") (pinfunction "1_1") (pintype "passive"))
      (node (ref "R49") (pin "1") (pinfunction "1_1") (pintype "passive"))
      (node (ref "R5") (pin "1") (pinfunction "1_1") (pintype "passive"))
      (node (ref "R904") (pin "1") (pinfunction "1_1") (pintype "passive"))
      (node (ref "SW1") (pin "3") (pinfunction "P_3") (pintype "passive"))
      (node (ref "SW1") (pin "4") (pinfunction "P1_4") (pintype "passive"))
      (node (ref "SW2") (pin "3") (pinfunction "P_3") (pintype "passive"))
      (node (ref "SW2") (pin "4") (pinfunction "P1_4") (pintype "passive"))
      (node (ref "SW3") (pin "3") (pinfunction "P_3") (pintype "passive"))
      (node (ref "SW3") (pin "4") (pinfunction "P1_4") (pintype "passive"))
      (node (ref "SW4") (pin "3") (pinfunction "P_3") (pintype "passive"))
      (node (ref "SW4") (pin "4") (pinfunction "P1_4") (pintype "passive"))
      (node (ref "SW5") (pin "3") (pinfunction "P_3") (pintype "passive"))
      (node (ref "SW5") (pin "4") (pinfunction "P1_4") (pintype "passive"))
      (node (ref "TRA") (pin "P$1") (pinfunction "5_P$1") (pintype "passive"))
      (node (ref "TRA") (pin "P$2") (pinfunction "4_P$2") (pintype "passive"))
      (node (ref "TRF") (pin "P$1") (pinfunction "5_P$1") (pintype "passive"))
      (node (ref "U3") (pin "2") (pinfunction "GND_2") (pintype "power_in"))
      (node (ref "USB") (pin "5") (pinfunction "5_5") (pintype "passive"))
      (node (ref "X3") (pin "4") (pinfunction "4_4") (pintype "passive"))
      (node (ref "X5") (pin "GND") (pinfunction "GND_GND") (pintype "bidirectional"))
    )
    (net (code "50") (name "Net-(BUS-Pad1)") (class "Default")
      (node (ref "BUS") (pin "1") (pinfunction "1_1") (pintype "passive"))
      (node (ref "R53") (pin "1") (pinfunction "1_1") (pintype "passive"))
    )
    (net (code "51") (name "Net-(C10-Pad1)") (class "Default")
      (node (ref "C10") (pin "1") (pinfunction "1_1") (pintype "passive"))
      (node (ref "R14") (pin "1") (pinfunction "1_1") (pintype "passive"))
      (node (ref "R15") (pin "1") (pinfunction "1_1") (pintype "passive"))
      (node (ref "R16") (pin "2") (pinfunction "2_2") (pintype "passive"))
    )
    (net (code "52") (name "Net-(C13-Pad1)") (class "Default")
      (node (ref "C13") (pin "1") (pinfunction "1_1") (pintype "passive"))
      (node (ref "R17") (pin "2") (pinfunction "2_2") (pintype "passive"))
      (node (ref "R18") (pin "1") (pinfunction "1_1") (pintype "passive"))
      (node (ref "R19") (pin "2") (pinfunction "2_2") (pintype "passive"))
    )
    (net (code "53") (name "Net-(C14-Pad1)") (class "Default")
      (node (ref "C14") (pin "1") (pinfunction "1_1") (pintype "passive"))
      (node (ref "R20") (pin "1") (pinfunction "1_1") (pintype "passive"))
      (node (ref "R21") (pin "2") (pinfunction "2_2") (pintype "passive"))
      (node (ref "R22") (pin "2") (pinfunction "2_2") (pintype "passive"))
    )
    (net (code "54") (name "Net-(C18-Pad1)") (class "Default")
      (node (ref "C18") (pin "1") (pinfunction "1_1") (pintype "passive"))
      (node (ref "R25") (pin "1") (pinfunction "1_1") (pintype "passive"))
      (node (ref "R26") (pin "2") (pinfunction "2_2") (pintype "passive"))
      (node (ref "R28") (pin "1") (pinfunction "1_1") (pintype "passive"))
    )
    (net (code "55") (name "Net-(CV_A-3)") (class "Default")
      (node (ref "CV_A") (pin "P$3") (pinfunction "3_P$3") (pintype "passive"))
      (node (ref "R8") (pin "1") (pinfunction "1_1") (pintype "passive"))
    )
    (net (code "56") (name "Net-(CV_B-3)") (class "Default")
      (node (ref "CV_B") (pin "P$3") (pinfunction "3_P$3") (pintype "passive"))
      (node (ref "R31") (pin "1") (pinfunction "1_1") (pintype "passive"))
    )
    (net (code "57") (name "Net-(CV_F-3)") (class "Default")
      (node (ref "CV_F") (pin "P$3") (pinfunction "3_P$3") (pintype "passive"))
      (node (ref "R30") (pin "1") (pinfunction "1_1") (pintype "passive"))
    )
    (net (code "58") (name "Net-(CV_G-3)") (class "Default")
      (node (ref "CV_G") (pin "P$3") (pinfunction "3_P$3") (pintype "passive"))
      (node (ref "R33") (pin "1") (pinfunction "1_1") (pintype "passive"))
    )
    (net (code "59") (name "Net-(D1-C1A2)") (class "Default")
      (node (ref "D1") (pin "3") (pinfunction "C1A2_3") (pintype "passive"))
      (node (ref "R39") (pin "2") (pinfunction "2_2") (pintype "passive"))
      (node (ref "R40") (pin "1") (pinfunction "1_1") (pintype "passive"))
    )
    (net (code "60") (name "Net-(D2-C1A2)") (class "Default")
      (node (ref "D2") (pin "3") (pinfunction "C1A2_3") (pintype "passive"))
      (node (ref "R41") (pin "2") (pinfunction "2_2") (pintype "passive"))
      (node (ref "R42") (pin "1") (pinfunction "1_1") (pintype "passive"))
    )
    (net (code "61") (name "Net-(IC2A-+IN)") (class "Default")
      (node (ref "IC2") (pin "3") (pinfunction "+IN_3") (pintype "input"))
      (node (ref "R3") (pin "2") (pinfunction "2_2") (pintype "passive"))
      (node (ref "R4") (pin "1") (pinfunction "1_1") (pintype "passive"))
    )
    (net (code "62") (name "Net-(IC2A--IN)") (class "Default")
      (node (ref "IC2") (pin "2") (pinfunction "-IN_2") (pintype "input"))
      (node (ref "R1") (pin "2") (pinfunction "2_2") (pintype "passive"))
      (node (ref "R2") (pin "1") (pinfunction "1_1") (pintype "passive"))
    )
    (net (code "63") (name "Net-(IC2A-OUT)") (class "Default")
      (node (ref "IC2") (pin "1") (pinfunction "OUT_1") (pintype "output"))
      (node (ref "R1") (pin "1") (pinfunction "1_1") (pintype "passive"))
      (node (ref "R7") (pin "2") (pinfunction "2_2") (pintype "passive"))
    )
    (net (code "64") (name "Net-(IC2B-+IN)") (class "Default")
      (node (ref "IC2") (pin "5") (pinfunction "+IN_5") (pintype "input"))
      (node (ref "R5") (pin "2") (pinfunction "2_2") (pintype "passive"))
      (node (ref "R6") (pin "1") (pinfunction "1_1") (pintype "passive"))
    )
    (net (code "65") (name "Net-(IC2B--IN)") (class "Default")
      (node (ref "IC2") (pin "6") (pinfunction "-IN_6") (pintype "input"))
      (node (ref "R11") (pin "2") (pinfunction "2_2") (pintype "passive"))
      (node (ref "R12") (pin "1") (pinfunction "1_1") (pintype "passive"))
    )
    (net (code "66") (name "Net-(IC2B-OUT)") (class "Default")
      (node (ref "IC2") (pin "7") (pinfunction "OUT_7") (pintype "output"))
      (node (ref "R10") (pin "2") (pinfunction "2_2") (pintype "passive"))
      (node (ref "R11") (pin "1") (pinfunction "1_1") (pintype "passive"))
    )
    (net (code "67") (name "Net-(IC3A-+IN)") (class "Default")
      (node (ref "C21") (pin "1") (pinfunction "1_1") (pintype "passive"))
      (node (ref "IC3") (pin "3") (pinfunction "+IN_3") (pintype "input"))
      (node (ref "R18") (pin "2") (pinfunction "2_2") (pintype "passive"))
    )
    (net (code "68") (name "Net-(IC3A--IN)") (class "Default")
      (node (ref "C11") (pin "1") (pinfunction "1_1") (pintype "passive"))
      (node (ref "IC3") (pin "2") (pinfunction "-IN_2") (pintype "input"))
      (node (ref "R15") (pin "2") (pinfunction "2_2") (pintype "passive"))
    )
    (net (code "69") (name "Net-(IC3A-OUT)") (class "Default")
      (node (ref "C11") (pin "2") (pinfunction "2_2") (pintype "passive"))
      (node (ref "IC3") (pin "1") (pinfunction "OUT_1") (pintype "output"))
      (node (ref "R13") (pin "1") (pinfunction "1_1") (pintype "passive"))
      (node (ref "R14") (pin "2") (pinfunction "2_2") (pintype "passive"))
    )
    (net (code "70") (name "Net-(IC3B-+IN)") (class "Default")
      (node (ref "C22") (pin "1") (pinfunction "1_1") (pintype "passive"))
      (node (ref "IC3") (pin "5") (pinfunction "+IN_5") (pintype "input"))
      (node (ref "R20") (pin "2") (pinfunction "2_2") (pintype "passive"))
    )
    (net (code "71") (name "Net-(IC3B--IN)") (class "Default")
      (node (ref "C16") (pin "1") (pinfunction "1_1") (pintype "passive"))
      (node (ref "IC3") (pin "6") (pinfunction "-IN_6") (pintype "input"))
      (node (ref "R25") (pin "2") (pinfunction "2_2") (pintype "passive"))
    )
    (net (code "72") (name "Net-(IC3B-OUT)") (class "Default")
      (node (ref "C16") (pin "2") (pinfunction "2_2") (pintype "passive"))
      (node (ref "IC3") (pin "7") (pinfunction "OUT_7") (pintype "output"))
      (node (ref "R27") (pin "1") (pinfunction "1_1") (pintype "passive"))
      (node (ref "R28") (pin "2") (pinfunction "2_2") (pintype "passive"))
    )
    (net (code "73") (name "Net-(IC4A--IN)") (class "Default")
      (node (ref "IC4") (pin "2") (pinfunction "-IN_2") (pintype "input"))
      (node (ref "R24") (pin "1") (pinfunction "1_1") (pintype "passive"))
      (node (ref "R31") (pin "2") (pinfunction "2_2") (pintype "passive"))
      (node (ref "R32") (pin "2") (pinfunction "2_2") (pintype "passive"))
    )
    (net (code "74") (name "Net-(IC4A-OUT)") (class "Default")
      (node (ref "IC4") (pin "1") (pinfunction "OUT_1") (pintype "output"))
      (node (ref "R24") (pin "2") (pinfunction "2_2") (pintype "passive"))
      (node (ref "R42") (pin "2") (pinfunction "2_2") (pintype "passive"))
    )
    (net (code "75") (name "Net-(IC4B--IN)") (class "Default")
      (node (ref "C24") (pin "1") (pinfunction "1_1") (pintype "passive"))
      (node (ref "IC4") (pin "6") (pinfunction "-IN_6") (pintype "input"))
      (node (ref "R36") (pin "2") (pinfunction "2_2") (pintype "passive"))
      (node (ref "R37") (pin "2") (pinfunction "2_2") (pintype "passive"))
    )
    (net (code "76") (name "Net-(IC4B-OUT)") (class "Default")
      (node (ref "C24") (pin "2") (pinfunction "2_2") (pintype "passive"))
      (node (ref "IC4") (pin "7") (pinfunction "OUT_7") (pintype "output"))
      (node (ref "R33") (pin "2") (pinfunction "2_2") (pintype "passive"))
      (node (ref "R36") (pin "1") (pinfunction "1_1") (pintype "passive"))
    )
    (net (code "77") (name "Net-(IC4C--IN)") (class "Default")
      (node (ref "C23") (pin "1") (pinfunction "1_1") (pintype "passive"))
      (node (ref "IC4") (pin "9") (pinfunction "-IN_9") (pintype "input"))
      (node (ref "R34") (pin "2") (pinfunction "2_2") (pintype "passive"))
      (node (ref "R35") (pin "2") (pinfunction "2_2") (pintype "passive"))
    )
    (net (code "78") (name "Net-(IC4C-OUT)") (class "Default")
      (node (ref "C23") (pin "2") (pinfunction "2_2") (pintype "passive"))
      (node (ref "IC4") (pin "8") (pinfunction "OUT_8") (pintype "output"))
      (node (ref "R30") (pin "2") (pinfunction "2_2") (pintype "passive"))
      (node (ref "R34") (pin "1") (pinfunction "1_1") (pintype "passive"))
    )
    (net (code "79") (name "Net-(IC4D--IN)") (class "Default")
      (node (ref "IC4") (pin "13") (pinfunction "-IN_13") (pintype "input"))
      (node (ref "R23") (pin "1") (pinfunction "1_1") (pintype "passive"))
      (node (ref "R8") (pin "2") (pinfunction "2_2") (pintype "passive"))
      (node (ref "R9") (pin "2") (pinfunction "2_2") (pintype "passive"))
    )
    (net (code "80") (name "Net-(IC4D-OUT)") (class "Default")
      (node (ref "IC4") (pin "14") (pinfunction "OUT_14") (pintype "output"))
      (node (ref "R23") (pin "2") (pinfunction "2_2") (pintype "passive"))
      (node (ref "R40") (pin "2") (pinfunction "2_2") (pintype "passive"))
    )
    (net (code "81") (name "Net-(JP13-Pad2)") (class "Default")
      (node (ref "JP13") (pin "2") (pinfunction "2_2") (pintype "passive"))
      (node (ref "X5") (pin "VBUS") (pinfunction "VBUS_VBUS") (pintype "bidirectional"))
    )
    (net (code "82") (name "Net-(LED1-CBLUE)") (class "Default")
      (node (ref "LED1") (pin "P4") (pinfunction "CBLUE_P4") (pintype "passive"))
      (node (ref "R44") (pin "1") (pinfunction "1_1") (pintype "passive"))
    )
    (net (code "83") (name "Net-(LED1-CGREEN)") (class "Default")
      (node (ref "LED1") (pin "P2") (pinfunction "CGREEN_P2") (pintype "passive"))
      (node (ref "R45") (pin "1") (pinfunction "1_1") (pintype "passive"))
    )
    (net (code "84") (name "Net-(LED1-CRED)") (class "Default")
      (node (ref "LED1") (pin "P1") (pinfunction "CRED_P1") (pintype "passive"))
      (node (ref "R43") (pin "1") (pinfunction "1_1") (pintype "passive"))
    )
    (net (code "85") (name "Net-(POT_A-Pad2)") (class "Default")
      (node (ref "POT_A") (pin "2") (pinfunction "2_2") (pintype "bidirectional"))
      (node (ref "R9") (pin "1") (pinfunction "1_1") (pintype "passive"))
    )
    (net (code "86") (name "Net-(POT_B-Pad2)") (class "Default")
      (node (ref "POT_B") (pin "2") (pinfunction "2_2") (pintype "bidirectional"))
      (node (ref "R32") (pin "1") (pinfunction "1_1") (pintype "passive"))
    )
    (net (code "87") (name "Net-(Q1-D)") (class "Default")
      (node (ref "JP8") (pin "10") (pinfunction "10_10") (pintype "passive"))
      (node (ref "JP8") (pin "9") (pinfunction "9_9") (pintype "passive"))
      (node (ref "Q1") (pin "3") (pinfunction "D_3") (pintype "passive"))
    )
    (net (code "88") (name "Net-(Q2-D)") (class "Default")
      (node (ref "JP8") (pin "1") (pinfunction "1_1") (pintype "passive"))
      (node (ref "JP8") (pin "2") (pinfunction "2_2") (pintype "passive"))
      (node (ref "Q2") (pin "3") (pinfunction "D_3") (pintype "passive"))
    )
    (net (code "89") (name "Net-(Q3-B)") (class "Default")
      (node (ref "Q3") (pin "1") (pinfunction "B_1") (pintype "passive"))
      (node (ref "R49") (pin "2") (pinfunction "2_2") (pintype "passive"))
      (node (ref "R50") (pin "2") (pinfunction "2_2") (pintype "passive"))
    )
    (net (code "90") (name "Net-(Q903-B)") (class "Default")
      (node (ref "Q903") (pin "1") (pinfunction "B_1") (pintype "passive"))
      (node (ref "R38") (pin "1") (pinfunction "1_1") (pintype "passive"))
    )
    (net (code "91") (name "Net-(Q903-C)") (class "Default")
      (node (ref "Q903") (pin "3") (pinfunction "C_3") (pintype "passive"))
      (node (ref "R902") (pin "2") (pinfunction "2_2") (pintype "passive"))
      (node (ref "R903") (pin "1") (pinfunction "1_1") (pintype "passive"))
    )
    (net (code "92") (name "Net-(TRA-3)") (class "Default")
      (node (ref "R50") (pin "1") (pinfunction "1_1") (pintype "passive"))
      (node (ref "TRA") (pin "P$3") (pinfunction "3_P$3") (pintype "passive"))
    )
    (net (code "93") (name "unconnected-(OUT_L-4-PadP$2)") (class "Default")
      (node (ref "OUT_L") (pin "P$2") (pinfunction "4_P$2") (pintype "passive"))
    )
    (net (code "94") (name "unconnected-(OUT_R-4-PadP$2)") (class "Default")
      (node (ref "OUT_R") (pin "P$2") (pinfunction "4_P$2") (pintype "passive"))
    )
    (net (code "95") (name "unconnected-(TRF-4-PadP$2)") (class "Default")
      (node (ref "TRF") (pin "P$2") (pinfunction "4_P$2") (pintype "passive"))
    )
    (net (code "96") (name "unconnected-(X3-S1-PadM1)") (class "Default")
      (node (ref "X3") (pin "M1") (pinfunction "S1_M1") (pintype "passive"))
    )
    (net (code "97") (name "unconnected-(X3-S2-PadM2)") (class "Default")
      (node (ref "X3") (pin "M2") (pinfunction "S2_M2") (pintype "passive"))
    )
  )
)
